# BackplaneBoard.net
KiCad netlist of a schematic drawn in EAGLE
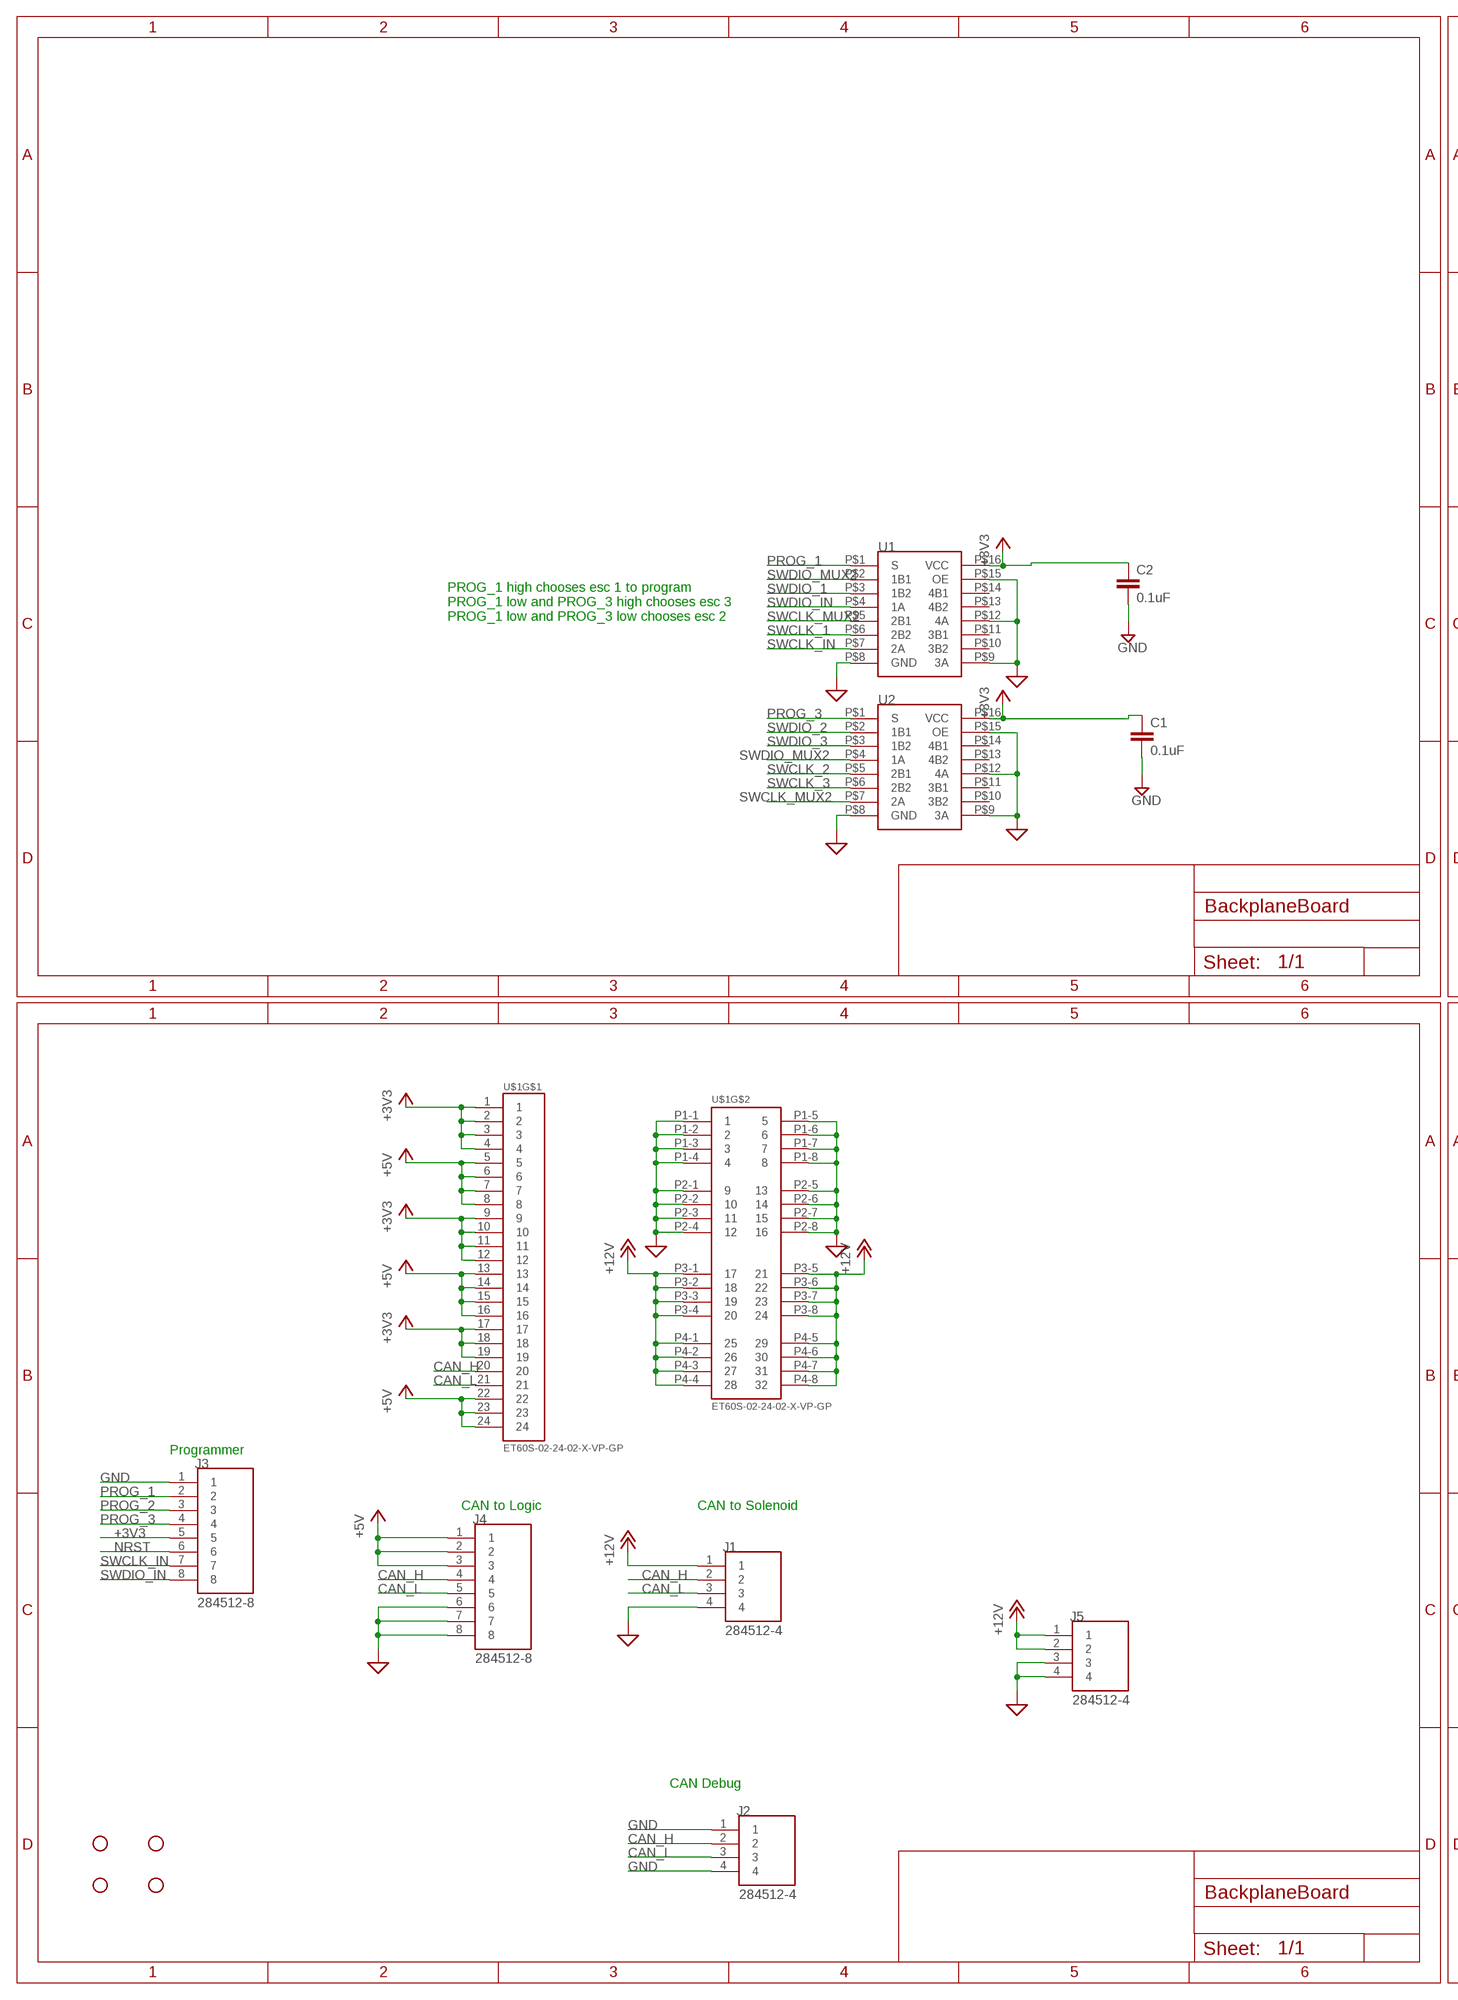
[diagram p0: schematic, sheet 1, part 1 of 2]
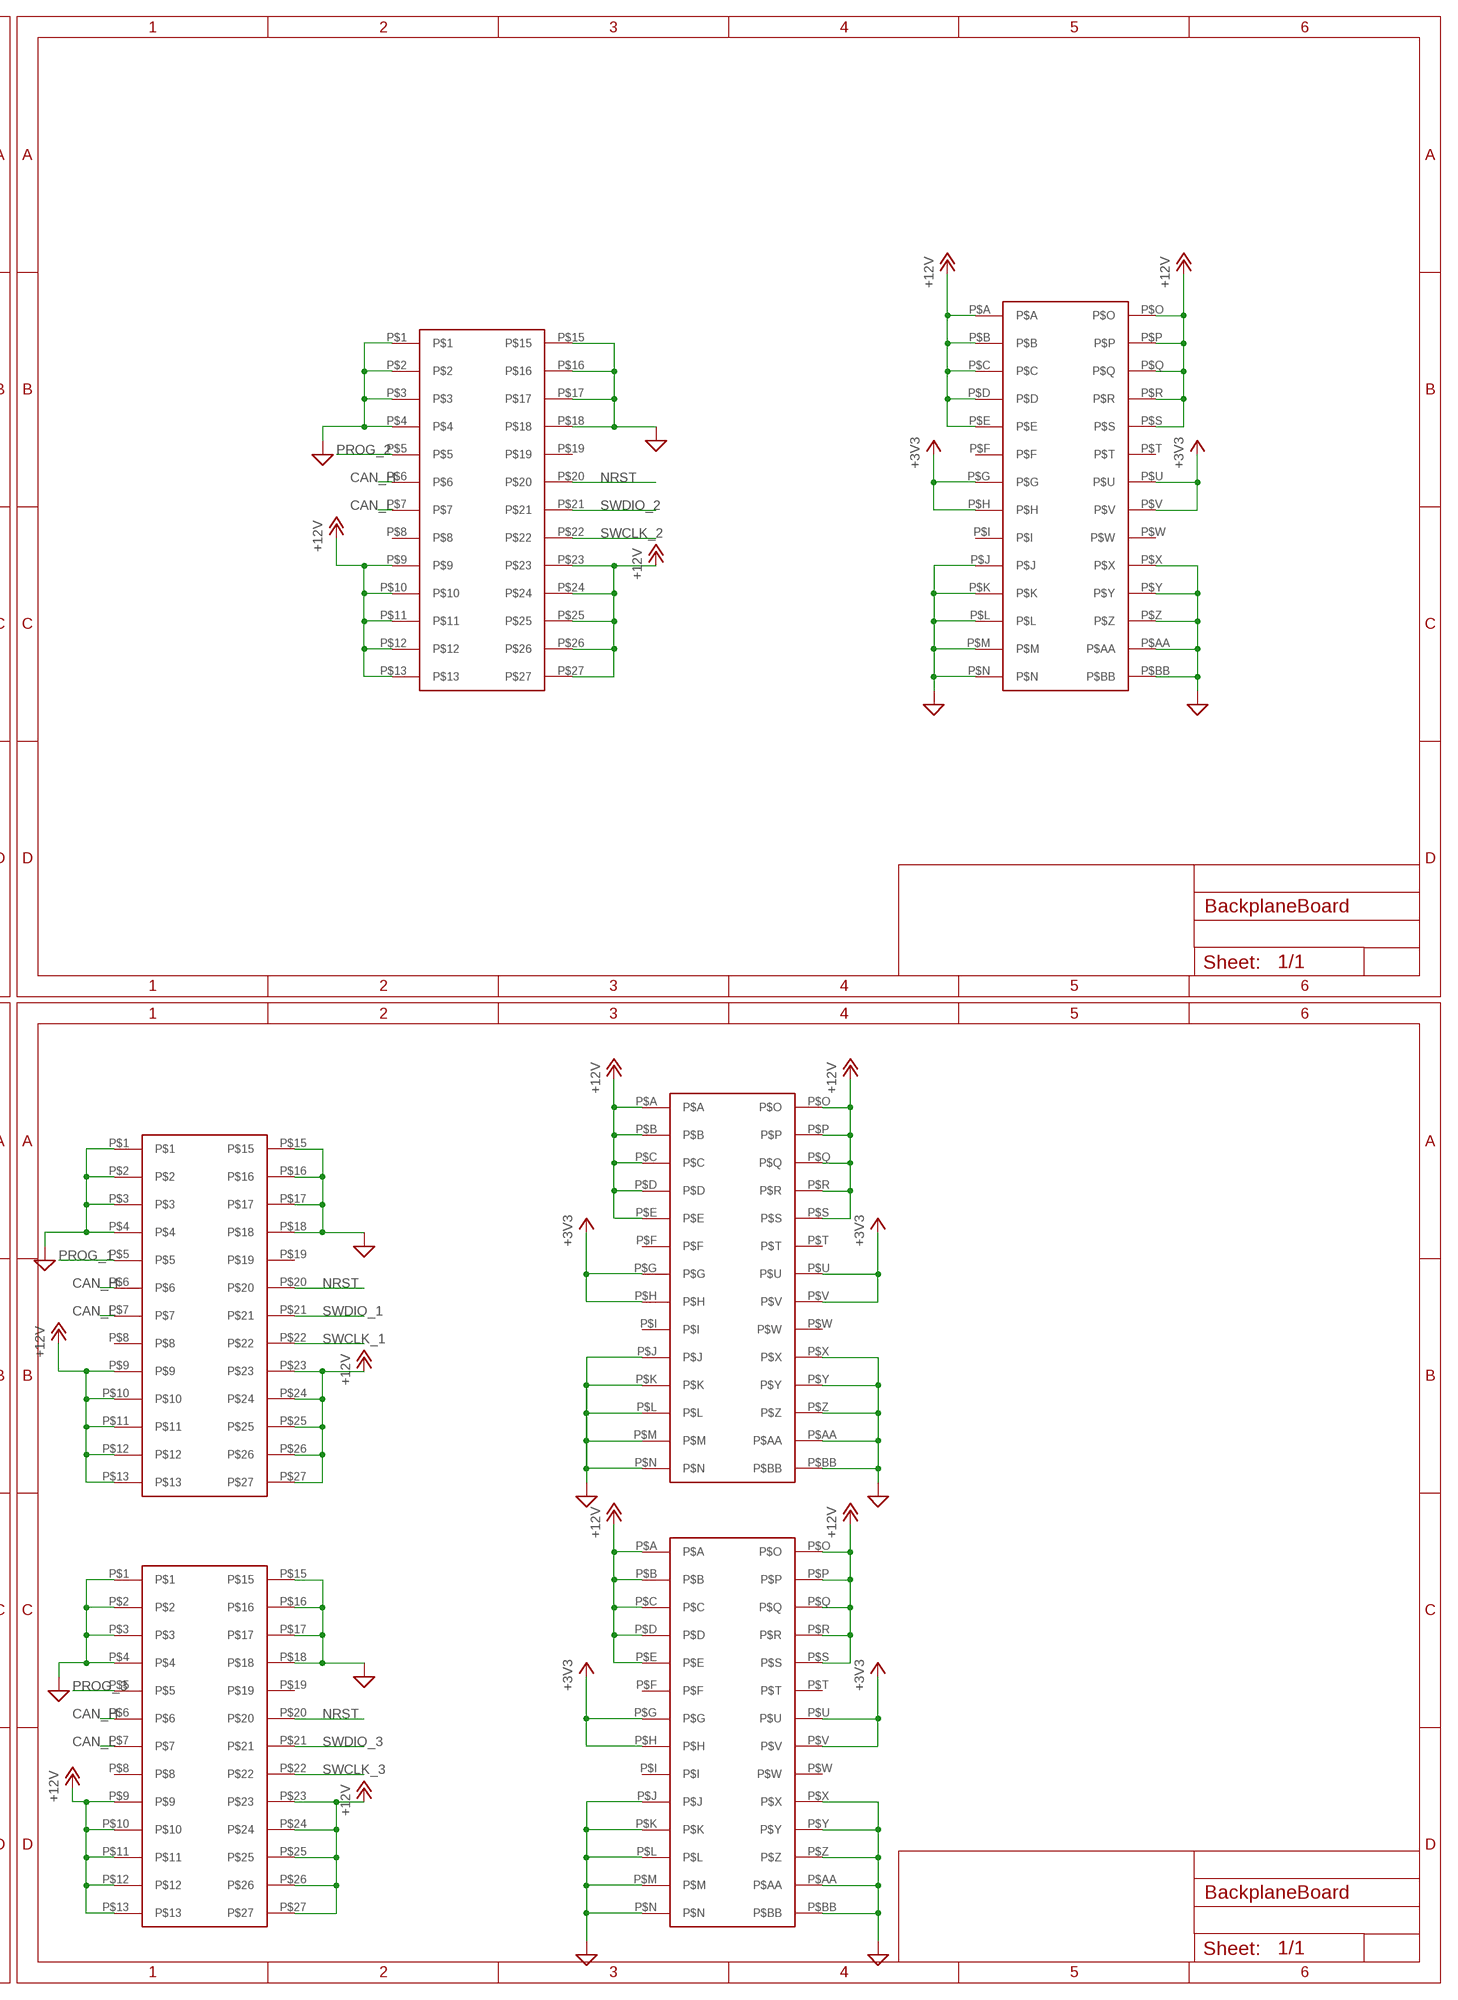
[diagram p1: schematic, sheet 1, part 2 of 2]

(export (version "E")
  (design (tool "Eeschema 10.0.6"))
  (components
    (comp (ref "C1")
      (value "0.1uF")
      (footprint "eagle-import:0603")
      (libsource (lib "eagle-import") (part "0.1UF-0603-25V-(+80/-20%)"))
    )
    (comp (ref "C2")
      (value "0.1uF")
      (footprint "eagle-import:0603")
      (libsource (lib "eagle-import") (part "0.1UF-0603-25V-(+80/-20%)"))
    )
    (comp (ref "H1")
      (value "STAND-OFF")
      (footprint "eagle-import:STAND-OFF")
      (libsource (lib "eagle-import") (part "STAND-OFF"))
    )
    (comp (ref "H2")
      (value "STAND-OFF")
      (footprint "eagle-import:STAND-OFF")
      (libsource (lib "eagle-import") (part "STAND-OFF"))
    )
    (comp (ref "H3")
      (value "STAND-OFF")
      (footprint "eagle-import:STAND-OFF")
      (libsource (lib "eagle-import") (part "STAND-OFF"))
    )
    (comp (ref "H4")
      (value "STAND-OFF")
      (footprint "eagle-import:STAND-OFF")
      (libsource (lib "eagle-import") (part "STAND-OFF"))
    )
    (comp (ref "J1")
      (value "284512-4")
      (footprint "eagle-import:TE_284512-4")
      (fields (field (name "MANUFACTURER") "TE"))
      (libsource (lib "eagle-import") (part "284512-4"))
    )
    (comp (ref "J2")
      (value "284512-4")
      (footprint "eagle-import:TE_284512-4")
      (fields (field (name "MANUFACTURER") "TE"))
      (libsource (lib "eagle-import") (part "284512-4"))
    )
    (comp (ref "J3")
      (value "284512-8")
      (footprint "eagle-import:TE_284512-8")
      (fields (field (name "MANUFACTURER") "TE"))
      (libsource (lib "eagle-import") (part "284512-8"))
    )
    (comp (ref "J4")
      (value "284512-8")
      (footprint "eagle-import:TE_284512-8")
      (fields (field (name "MANUFACTURER") "TE"))
      (libsource (lib "eagle-import") (part "284512-8"))
    )
    (comp (ref "J5")
      (value "284512-4")
      (footprint "eagle-import:TE_284512-4")
      (fields (field (name "MANUFACTURER") "TE"))
      (libsource (lib "eagle-import") (part "284512-4"))
    )
    (comp (ref "U$1")
      (value "ET60S-02-24-02-X-VP-GP")
      (footprint "eagle-import:ET60S-02-24-02-X-VP-GP")
      (libsource (lib "eagle-import") (part "ET60S-02-24-02-X-VP-GP"))
    )
    (comp (ref "U$2")
      (value "ESC2BACKPLANE")
      (footprint "eagle-import:ESC2BACKPLANE_WHOLE")
      (libsource (lib "eagle-import") (part "ESC2BACKPLANE"))
    )
    (comp (ref "U$3")
      (value "ESC2BACKPLANE")
      (footprint "eagle-import:ESC2BACKPLANE_WHOLE")
      (libsource (lib "eagle-import") (part "ESC2BACKPLANE"))
    )
    (comp (ref "U$4")
      (value "ESC2BACKPLANE")
      (footprint "eagle-import:ESC2BACKPLANE_WHOLE")
      (libsource (lib "eagle-import") (part "ESC2BACKPLANE"))
    )
    (comp (ref "U1")
      (value "SN74CBTLV3257PWR")
      (footprint "eagle-import:SN74CBTLV3257PWR")
      (libsource (lib "eagle-import") (part "SN74CBTLV3257PWR"))
    )
    (comp (ref "U2")
      (value "SN74CBTLV3257PWR")
      (footprint "eagle-import:SN74CBTLV3257PWR")
      (libsource (lib "eagle-import") (part "SN74CBTLV3257PWR"))
    )
  )
  (nets
    (net (code "1") (name "+3V3") (class "Default")
      (node (ref "C1") (pin "1") (pinfunction "1_1") (pintype "passive"))
      (node (ref "C2") (pin "1") (pinfunction "1_1") (pintype "passive"))
      (node (ref "J3") (pin "5") (pinfunction "5_5") (pintype "passive"))
      (node (ref "U$1") (pin "1") (pinfunction "1_1") (pintype "bidirectional"))
      (node (ref "U$1") (pin "10") (pinfunction "10_10") (pintype "bidirectional"))
      (node (ref "U$1") (pin "11") (pinfunction "11_11") (pintype "bidirectional"))
      (node (ref "U$1") (pin "12") (pinfunction "12_12") (pintype "bidirectional"))
      (node (ref "U$1") (pin "17") (pinfunction "17_17") (pintype "bidirectional"))
      (node (ref "U$1") (pin "18") (pinfunction "18_18") (pintype "bidirectional"))
      (node (ref "U$1") (pin "19") (pinfunction "19_19") (pintype "bidirectional"))
      (node (ref "U$1") (pin "2") (pinfunction "2_2") (pintype "bidirectional"))
      (node (ref "U$1") (pin "3") (pinfunction "3_3") (pintype "bidirectional"))
      (node (ref "U$1") (pin "4") (pinfunction "4_4") (pintype "bidirectional"))
      (node (ref "U$1") (pin "9") (pinfunction "9_9") (pintype "bidirectional"))
      (node (ref "U$2") (pin "P$G") (pinfunction "P$G_P$G") (pintype "bidirectional"))
      (node (ref "U$2") (pin "P$H") (pinfunction "P$H_P$H") (pintype "bidirectional"))
      (node (ref "U$2") (pin "P$U") (pinfunction "P$U_P$U") (pintype "bidirectional"))
      (node (ref "U$2") (pin "P$V") (pinfunction "P$V_P$V") (pintype "bidirectional"))
      (node (ref "U$3") (pin "P$G") (pinfunction "P$G_P$G") (pintype "bidirectional"))
      (node (ref "U$3") (pin "P$H") (pinfunction "P$H_P$H") (pintype "bidirectional"))
      (node (ref "U$3") (pin "P$U") (pinfunction "P$U_P$U") (pintype "bidirectional"))
      (node (ref "U$3") (pin "P$V") (pinfunction "P$V_P$V") (pintype "bidirectional"))
      (node (ref "U$4") (pin "P$G") (pinfunction "P$G_P$G") (pintype "bidirectional"))
      (node (ref "U$4") (pin "P$H") (pinfunction "P$H_P$H") (pintype "bidirectional"))
      (node (ref "U$4") (pin "P$U") (pinfunction "P$U_P$U") (pintype "bidirectional"))
      (node (ref "U$4") (pin "P$V") (pinfunction "P$V_P$V") (pintype "bidirectional"))
      (node (ref "U1") (pin "P$16") (pinfunction "VCC_P$16") (pintype "bidirectional"))
      (node (ref "U2") (pin "P$16") (pinfunction "VCC_P$16") (pintype "bidirectional"))
    )
    (net (code "2") (name "+5V") (class "Default")
      (node (ref "J4") (pin "1") (pinfunction "1_1") (pintype "passive"))
      (node (ref "J4") (pin "2") (pinfunction "2_2") (pintype "passive"))
      (node (ref "J4") (pin "3") (pinfunction "3_3") (pintype "passive"))
      (node (ref "U$1") (pin "13") (pinfunction "13_13") (pintype "bidirectional"))
      (node (ref "U$1") (pin "14") (pinfunction "14_14") (pintype "bidirectional"))
      (node (ref "U$1") (pin "15") (pinfunction "15_15") (pintype "bidirectional"))
      (node (ref "U$1") (pin "16") (pinfunction "16_16") (pintype "bidirectional"))
      (node (ref "U$1") (pin "22") (pinfunction "22_22") (pintype "bidirectional"))
      (node (ref "U$1") (pin "23") (pinfunction "23_23") (pintype "bidirectional"))
      (node (ref "U$1") (pin "24") (pinfunction "24_24") (pintype "bidirectional"))
      (node (ref "U$1") (pin "5") (pinfunction "5_5") (pintype "bidirectional"))
      (node (ref "U$1") (pin "6") (pinfunction "6_6") (pintype "bidirectional"))
      (node (ref "U$1") (pin "7") (pinfunction "7_7") (pintype "bidirectional"))
      (node (ref "U$1") (pin "8") (pinfunction "8_8") (pintype "bidirectional"))
    )
    (net (code "3") (name "+12V") (class "Default")
      (node (ref "J1") (pin "1") (pinfunction "1_1") (pintype "passive"))
      (node (ref "J5") (pin "1") (pinfunction "1_1") (pintype "passive"))
      (node (ref "J5") (pin "2") (pinfunction "2_2") (pintype "passive"))
      (node (ref "U$1") (pin "P3-1") (pinfunction "17_P3-1") (pintype "bidirectional"))
      (node (ref "U$1") (pin "P3-2") (pinfunction "18_P3-2") (pintype "bidirectional"))
      (node (ref "U$1") (pin "P3-3") (pinfunction "19_P3-3") (pintype "bidirectional"))
      (node (ref "U$1") (pin "P3-4") (pinfunction "20_P3-4") (pintype "bidirectional"))
      (node (ref "U$1") (pin "P3-5") (pinfunction "21_P3-5") (pintype "bidirectional"))
      (node (ref "U$1") (pin "P3-6") (pinfunction "22_P3-6") (pintype "bidirectional"))
      (node (ref "U$1") (pin "P3-7") (pinfunction "23_P3-7") (pintype "bidirectional"))
      (node (ref "U$1") (pin "P3-8") (pinfunction "24_P3-8") (pintype "bidirectional"))
      (node (ref "U$1") (pin "P4-1") (pinfunction "25_P4-1") (pintype "bidirectional"))
      (node (ref "U$1") (pin "P4-2") (pinfunction "26_P4-2") (pintype "bidirectional"))
      (node (ref "U$1") (pin "P4-3") (pinfunction "27_P4-3") (pintype "bidirectional"))
      (node (ref "U$1") (pin "P4-4") (pinfunction "28_P4-4") (pintype "bidirectional"))
      (node (ref "U$1") (pin "P4-5") (pinfunction "29_P4-5") (pintype "bidirectional"))
      (node (ref "U$1") (pin "P4-6") (pinfunction "30_P4-6") (pintype "bidirectional"))
      (node (ref "U$1") (pin "P4-7") (pinfunction "31_P4-7") (pintype "bidirectional"))
      (node (ref "U$1") (pin "P4-8") (pinfunction "32_P4-8") (pintype "bidirectional"))
      (node (ref "U$2") (pin "P$10") (pinfunction "P$10_P$10") (pintype "bidirectional"))
      (node (ref "U$2") (pin "P$11") (pinfunction "P$11_P$11") (pintype "bidirectional"))
      (node (ref "U$2") (pin "P$12") (pinfunction "P$12_P$12") (pintype "bidirectional"))
      (node (ref "U$2") (pin "P$13") (pinfunction "P$13_P$13") (pintype "bidirectional"))
      (node (ref "U$2") (pin "P$23") (pinfunction "P$23_P$23") (pintype "bidirectional"))
      (node (ref "U$2") (pin "P$24") (pinfunction "P$24_P$24") (pintype "bidirectional"))
      (node (ref "U$2") (pin "P$25") (pinfunction "P$25_P$25") (pintype "bidirectional"))
      (node (ref "U$2") (pin "P$26") (pinfunction "P$26_P$26") (pintype "bidirectional"))
      (node (ref "U$2") (pin "P$27") (pinfunction "P$27_P$27") (pintype "bidirectional"))
      (node (ref "U$2") (pin "P$9") (pinfunction "P$9_P$9") (pintype "bidirectional"))
      (node (ref "U$2") (pin "P$A") (pinfunction "P$A_P$A") (pintype "bidirectional"))
      (node (ref "U$2") (pin "P$B") (pinfunction "P$B_P$B") (pintype "bidirectional"))
      (node (ref "U$2") (pin "P$C") (pinfunction "P$C_P$C") (pintype "bidirectional"))
      (node (ref "U$2") (pin "P$D") (pinfunction "P$D_P$D") (pintype "bidirectional"))
      (node (ref "U$2") (pin "P$E") (pinfunction "P$E_P$E") (pintype "bidirectional"))
      (node (ref "U$2") (pin "P$O") (pinfunction "P$O_P$O") (pintype "bidirectional"))
      (node (ref "U$2") (pin "P$P") (pinfunction "P$P_P$P") (pintype "bidirectional"))
      (node (ref "U$2") (pin "P$Q") (pinfunction "P$Q_P$Q") (pintype "bidirectional"))
      (node (ref "U$2") (pin "P$R") (pinfunction "P$R_P$R") (pintype "bidirectional"))
      (node (ref "U$2") (pin "P$S") (pinfunction "P$S_P$S") (pintype "bidirectional"))
      (node (ref "U$3") (pin "P$10") (pinfunction "P$10_P$10") (pintype "bidirectional"))
      (node (ref "U$3") (pin "P$11") (pinfunction "P$11_P$11") (pintype "bidirectional"))
      (node (ref "U$3") (pin "P$12") (pinfunction "P$12_P$12") (pintype "bidirectional"))
      (node (ref "U$3") (pin "P$13") (pinfunction "P$13_P$13") (pintype "bidirectional"))
      (node (ref "U$3") (pin "P$23") (pinfunction "P$23_P$23") (pintype "bidirectional"))
      (node (ref "U$3") (pin "P$24") (pinfunction "P$24_P$24") (pintype "bidirectional"))
      (node (ref "U$3") (pin "P$25") (pinfunction "P$25_P$25") (pintype "bidirectional"))
      (node (ref "U$3") (pin "P$26") (pinfunction "P$26_P$26") (pintype "bidirectional"))
      (node (ref "U$3") (pin "P$27") (pinfunction "P$27_P$27") (pintype "bidirectional"))
      (node (ref "U$3") (pin "P$9") (pinfunction "P$9_P$9") (pintype "bidirectional"))
      (node (ref "U$3") (pin "P$A") (pinfunction "P$A_P$A") (pintype "bidirectional"))
      (node (ref "U$3") (pin "P$B") (pinfunction "P$B_P$B") (pintype "bidirectional"))
      (node (ref "U$3") (pin "P$C") (pinfunction "P$C_P$C") (pintype "bidirectional"))
      (node (ref "U$3") (pin "P$D") (pinfunction "P$D_P$D") (pintype "bidirectional"))
      (node (ref "U$3") (pin "P$E") (pinfunction "P$E_P$E") (pintype "bidirectional"))
      (node (ref "U$3") (pin "P$O") (pinfunction "P$O_P$O") (pintype "bidirectional"))
      (node (ref "U$3") (pin "P$P") (pinfunction "P$P_P$P") (pintype "bidirectional"))
      (node (ref "U$3") (pin "P$Q") (pinfunction "P$Q_P$Q") (pintype "bidirectional"))
      (node (ref "U$3") (pin "P$R") (pinfunction "P$R_P$R") (pintype "bidirectional"))
      (node (ref "U$3") (pin "P$S") (pinfunction "P$S_P$S") (pintype "bidirectional"))
      (node (ref "U$4") (pin "P$10") (pinfunction "P$10_P$10") (pintype "bidirectional"))
      (node (ref "U$4") (pin "P$11") (pinfunction "P$11_P$11") (pintype "bidirectional"))
      (node (ref "U$4") (pin "P$12") (pinfunction "P$12_P$12") (pintype "bidirectional"))
      (node (ref "U$4") (pin "P$13") (pinfunction "P$13_P$13") (pintype "bidirectional"))
      (node (ref "U$4") (pin "P$23") (pinfunction "P$23_P$23") (pintype "bidirectional"))
      (node (ref "U$4") (pin "P$24") (pinfunction "P$24_P$24") (pintype "bidirectional"))
      (node (ref "U$4") (pin "P$25") (pinfunction "P$25_P$25") (pintype "bidirectional"))
      (node (ref "U$4") (pin "P$26") (pinfunction "P$26_P$26") (pintype "bidirectional"))
      (node (ref "U$4") (pin "P$27") (pinfunction "P$27_P$27") (pintype "bidirectional"))
      (node (ref "U$4") (pin "P$9") (pinfunction "P$9_P$9") (pintype "bidirectional"))
      (node (ref "U$4") (pin "P$A") (pinfunction "P$A_P$A") (pintype "bidirectional"))
      (node (ref "U$4") (pin "P$B") (pinfunction "P$B_P$B") (pintype "bidirectional"))
      (node (ref "U$4") (pin "P$C") (pinfunction "P$C_P$C") (pintype "bidirectional"))
      (node (ref "U$4") (pin "P$D") (pinfunction "P$D_P$D") (pintype "bidirectional"))
      (node (ref "U$4") (pin "P$E") (pinfunction "P$E_P$E") (pintype "bidirectional"))
      (node (ref "U$4") (pin "P$O") (pinfunction "P$O_P$O") (pintype "bidirectional"))
      (node (ref "U$4") (pin "P$P") (pinfunction "P$P_P$P") (pintype "bidirectional"))
      (node (ref "U$4") (pin "P$Q") (pinfunction "P$Q_P$Q") (pintype "bidirectional"))
      (node (ref "U$4") (pin "P$R") (pinfunction "P$R_P$R") (pintype "bidirectional"))
      (node (ref "U$4") (pin "P$S") (pinfunction "P$S_P$S") (pintype "bidirectional"))
    )
    (net (code "4") (name "/CAN_H") (class "Default")
      (node (ref "J1") (pin "2") (pinfunction "2_2") (pintype "passive"))
      (node (ref "J2") (pin "2") (pinfunction "2_2") (pintype "passive"))
      (node (ref "J4") (pin "4") (pinfunction "4_4") (pintype "passive"))
      (node (ref "U$1") (pin "20") (pinfunction "20_20") (pintype "bidirectional"))
      (node (ref "U$2") (pin "P$6") (pinfunction "P$6_P$6") (pintype "bidirectional"))
      (node (ref "U$3") (pin "P$6") (pinfunction "P$6_P$6") (pintype "bidirectional"))
      (node (ref "U$4") (pin "P$6") (pinfunction "P$6_P$6") (pintype "bidirectional"))
    )
    (net (code "5") (name "/CAN_L") (class "Default")
      (node (ref "J1") (pin "3") (pinfunction "3_3") (pintype "passive"))
      (node (ref "J2") (pin "3") (pinfunction "3_3") (pintype "passive"))
      (node (ref "J4") (pin "5") (pinfunction "5_5") (pintype "passive"))
      (node (ref "U$1") (pin "21") (pinfunction "21_21") (pintype "bidirectional"))
      (node (ref "U$2") (pin "P$7") (pinfunction "P$7_P$7") (pintype "bidirectional"))
      (node (ref "U$3") (pin "P$7") (pinfunction "P$7_P$7") (pintype "bidirectional"))
      (node (ref "U$4") (pin "P$7") (pinfunction "P$7_P$7") (pintype "bidirectional"))
    )
    (net (code "6") (name "/NRST") (class "Default")
      (node (ref "J3") (pin "6") (pinfunction "6_6") (pintype "passive"))
      (node (ref "U$2") (pin "P$20") (pinfunction "P$20_P$20") (pintype "bidirectional"))
      (node (ref "U$3") (pin "P$20") (pinfunction "P$20_P$20") (pintype "bidirectional"))
      (node (ref "U$4") (pin "P$20") (pinfunction "P$20_P$20") (pintype "bidirectional"))
    )
    (net (code "7") (name "/PROG_1") (class "Default")
      (node (ref "J3") (pin "2") (pinfunction "2_2") (pintype "passive"))
      (node (ref "U$2") (pin "P$5") (pinfunction "P$5_P$5") (pintype "bidirectional"))
      (node (ref "U1") (pin "P$1") (pinfunction "S_P$1") (pintype "bidirectional"))
    )
    (net (code "8") (name "/PROG_2") (class "Default")
      (node (ref "J3") (pin "3") (pinfunction "3_3") (pintype "passive"))
      (node (ref "U$3") (pin "P$5") (pinfunction "P$5_P$5") (pintype "bidirectional"))
    )
    (net (code "9") (name "/PROG_3") (class "Default")
      (node (ref "J3") (pin "4") (pinfunction "4_4") (pintype "passive"))
      (node (ref "U$4") (pin "P$5") (pinfunction "P$5_P$5") (pintype "bidirectional"))
      (node (ref "U2") (pin "P$1") (pinfunction "S_P$1") (pintype "bidirectional"))
    )
    (net (code "10") (name "/SWCLK_1") (class "Default")
      (node (ref "U$2") (pin "P$22") (pinfunction "P$22_P$22") (pintype "bidirectional"))
      (node (ref "U1") (pin "P$6") (pinfunction "2B2_P$6") (pintype "bidirectional"))
    )
    (net (code "11") (name "/SWCLK_2") (class "Default")
      (node (ref "U$3") (pin "P$22") (pinfunction "P$22_P$22") (pintype "bidirectional"))
      (node (ref "U2") (pin "P$5") (pinfunction "2B1_P$5") (pintype "bidirectional"))
    )
    (net (code "12") (name "/SWCLK_3") (class "Default")
      (node (ref "U$4") (pin "P$22") (pinfunction "P$22_P$22") (pintype "bidirectional"))
      (node (ref "U2") (pin "P$6") (pinfunction "2B2_P$6") (pintype "bidirectional"))
    )
    (net (code "13") (name "/SWCLK_IN") (class "Default")
      (node (ref "J3") (pin "7") (pinfunction "7_7") (pintype "passive"))
      (node (ref "U1") (pin "P$7") (pinfunction "2A_P$7") (pintype "bidirectional"))
    )
    (net (code "14") (name "/SWCLK_MUX2") (class "Default")
      (node (ref "U1") (pin "P$5") (pinfunction "2B1_P$5") (pintype "bidirectional"))
      (node (ref "U2") (pin "P$7") (pinfunction "2A_P$7") (pintype "bidirectional"))
    )
    (net (code "15") (name "/SWDIO_1") (class "Default")
      (node (ref "U$2") (pin "P$21") (pinfunction "P$21_P$21") (pintype "bidirectional"))
      (node (ref "U1") (pin "P$3") (pinfunction "1B2_P$3") (pintype "bidirectional"))
    )
    (net (code "16") (name "/SWDIO_2") (class "Default")
      (node (ref "U$3") (pin "P$21") (pinfunction "P$21_P$21") (pintype "bidirectional"))
      (node (ref "U2") (pin "P$2") (pinfunction "1B1_P$2") (pintype "bidirectional"))
    )
    (net (code "17") (name "/SWDIO_3") (class "Default")
      (node (ref "U$4") (pin "P$21") (pinfunction "P$21_P$21") (pintype "bidirectional"))
      (node (ref "U2") (pin "P$3") (pinfunction "1B2_P$3") (pintype "bidirectional"))
    )
    (net (code "18") (name "/SWDIO_IN") (class "Default")
      (node (ref "J3") (pin "8") (pinfunction "8_8") (pintype "passive"))
      (node (ref "U1") (pin "P$4") (pinfunction "1A_P$4") (pintype "bidirectional"))
    )
    (net (code "19") (name "/SWDIO_MUX2") (class "Default")
      (node (ref "U1") (pin "P$2") (pinfunction "1B1_P$2") (pintype "bidirectional"))
      (node (ref "U2") (pin "P$4") (pinfunction "1A_P$4") (pintype "bidirectional"))
    )
    (net (code "20") (name "GND") (class "Default")
      (node (ref "C1") (pin "2") (pinfunction "2_2") (pintype "passive"))
      (node (ref "C2") (pin "2") (pinfunction "2_2") (pintype "passive"))
      (node (ref "J1") (pin "4") (pinfunction "4_4") (pintype "passive"))
      (node (ref "J2") (pin "1") (pinfunction "1_1") (pintype "passive"))
      (node (ref "J2") (pin "4") (pinfunction "4_4") (pintype "passive"))
      (node (ref "J3") (pin "1") (pinfunction "1_1") (pintype "passive"))
      (node (ref "J4") (pin "6") (pinfunction "6_6") (pintype "passive"))
      (node (ref "J4") (pin "7") (pinfunction "7_7") (pintype "passive"))
      (node (ref "J4") (pin "8") (pinfunction "8_8") (pintype "passive"))
      (node (ref "J5") (pin "3") (pinfunction "3_3") (pintype "passive"))
      (node (ref "J5") (pin "4") (pinfunction "4_4") (pintype "passive"))
      (node (ref "U$1") (pin "P1-1") (pinfunction "1_P1-1") (pintype "bidirectional"))
      (node (ref "U$1") (pin "P1-2") (pinfunction "2_P1-2") (pintype "bidirectional"))
      (node (ref "U$1") (pin "P1-3") (pinfunction "3_P1-3") (pintype "bidirectional"))
      (node (ref "U$1") (pin "P1-4") (pinfunction "4_P1-4") (pintype "bidirectional"))
      (node (ref "U$1") (pin "P1-5") (pinfunction "5_P1-5") (pintype "bidirectional"))
      (node (ref "U$1") (pin "P1-6") (pinfunction "6_P1-6") (pintype "bidirectional"))
      (node (ref "U$1") (pin "P1-7") (pinfunction "7_P1-7") (pintype "bidirectional"))
      (node (ref "U$1") (pin "P1-8") (pinfunction "8_P1-8") (pintype "bidirectional"))
      (node (ref "U$1") (pin "P2-1") (pinfunction "9_P2-1") (pintype "bidirectional"))
      (node (ref "U$1") (pin "P2-2") (pinfunction "10_P2-2") (pintype "bidirectional"))
      (node (ref "U$1") (pin "P2-3") (pinfunction "11_P2-3") (pintype "bidirectional"))
      (node (ref "U$1") (pin "P2-4") (pinfunction "12_P2-4") (pintype "bidirectional"))
      (node (ref "U$1") (pin "P2-5") (pinfunction "13_P2-5") (pintype "bidirectional"))
      (node (ref "U$1") (pin "P2-6") (pinfunction "14_P2-6") (pintype "bidirectional"))
      (node (ref "U$1") (pin "P2-7") (pinfunction "15_P2-7") (pintype "bidirectional"))
      (node (ref "U$1") (pin "P2-8") (pinfunction "16_P2-8") (pintype "bidirectional"))
      (node (ref "U$2") (pin "P$1") (pinfunction "P$1_P$1") (pintype "bidirectional"))
      (node (ref "U$2") (pin "P$15") (pinfunction "P$15_P$15") (pintype "bidirectional"))
      (node (ref "U$2") (pin "P$16") (pinfunction "P$16_P$16") (pintype "bidirectional"))
      (node (ref "U$2") (pin "P$17") (pinfunction "P$17_P$17") (pintype "bidirectional"))
      (node (ref "U$2") (pin "P$18") (pinfunction "P$18_P$18") (pintype "bidirectional"))
      (node (ref "U$2") (pin "P$2") (pinfunction "P$2_P$2") (pintype "bidirectional"))
      (node (ref "U$2") (pin "P$3") (pinfunction "P$3_P$3") (pintype "bidirectional"))
      (node (ref "U$2") (pin "P$4") (pinfunction "P$4_P$4") (pintype "bidirectional"))
      (node (ref "U$2") (pin "P$AA") (pinfunction "P$AA_P$AA") (pintype "bidirectional"))
      (node (ref "U$2") (pin "P$BB") (pinfunction "P$BB_P$BB") (pintype "bidirectional"))
      (node (ref "U$2") (pin "P$J") (pinfunction "P$J_P$J") (pintype "bidirectional"))
      (node (ref "U$2") (pin "P$K") (pinfunction "P$K_P$K") (pintype "bidirectional"))
      (node (ref "U$2") (pin "P$L") (pinfunction "P$L_P$L") (pintype "bidirectional"))
      (node (ref "U$2") (pin "P$M") (pinfunction "P$M_P$M") (pintype "bidirectional"))
      (node (ref "U$2") (pin "P$N") (pinfunction "P$N_P$N") (pintype "bidirectional"))
      (node (ref "U$2") (pin "P$X") (pinfunction "P$X_P$X") (pintype "bidirectional"))
      (node (ref "U$2") (pin "P$Y") (pinfunction "P$Y_P$Y") (pintype "bidirectional"))
      (node (ref "U$2") (pin "P$Z") (pinfunction "P$Z_P$Z") (pintype "bidirectional"))
      (node (ref "U$3") (pin "P$1") (pinfunction "P$1_P$1") (pintype "bidirectional"))
      (node (ref "U$3") (pin "P$15") (pinfunction "P$15_P$15") (pintype "bidirectional"))
      (node (ref "U$3") (pin "P$16") (pinfunction "P$16_P$16") (pintype "bidirectional"))
      (node (ref "U$3") (pin "P$17") (pinfunction "P$17_P$17") (pintype "bidirectional"))
      (node (ref "U$3") (pin "P$18") (pinfunction "P$18_P$18") (pintype "bidirectional"))
      (node (ref "U$3") (pin "P$2") (pinfunction "P$2_P$2") (pintype "bidirectional"))
      (node (ref "U$3") (pin "P$3") (pinfunction "P$3_P$3") (pintype "bidirectional"))
      (node (ref "U$3") (pin "P$4") (pinfunction "P$4_P$4") (pintype "bidirectional"))
      (node (ref "U$3") (pin "P$AA") (pinfunction "P$AA_P$AA") (pintype "bidirectional"))
      (node (ref "U$3") (pin "P$BB") (pinfunction "P$BB_P$BB") (pintype "bidirectional"))
      (node (ref "U$3") (pin "P$J") (pinfunction "P$J_P$J") (pintype "bidirectional"))
      (node (ref "U$3") (pin "P$K") (pinfunction "P$K_P$K") (pintype "bidirectional"))
      (node (ref "U$3") (pin "P$L") (pinfunction "P$L_P$L") (pintype "bidirectional"))
      (node (ref "U$3") (pin "P$M") (pinfunction "P$M_P$M") (pintype "bidirectional"))
      (node (ref "U$3") (pin "P$N") (pinfunction "P$N_P$N") (pintype "bidirectional"))
      (node (ref "U$3") (pin "P$X") (pinfunction "P$X_P$X") (pintype "bidirectional"))
      (node (ref "U$3") (pin "P$Y") (pinfunction "P$Y_P$Y") (pintype "bidirectional"))
      (node (ref "U$3") (pin "P$Z") (pinfunction "P$Z_P$Z") (pintype "bidirectional"))
      (node (ref "U$4") (pin "P$1") (pinfunction "P$1_P$1") (pintype "bidirectional"))
      (node (ref "U$4") (pin "P$15") (pinfunction "P$15_P$15") (pintype "bidirectional"))
      (node (ref "U$4") (pin "P$16") (pinfunction "P$16_P$16") (pintype "bidirectional"))
      (node (ref "U$4") (pin "P$17") (pinfunction "P$17_P$17") (pintype "bidirectional"))
      (node (ref "U$4") (pin "P$18") (pinfunction "P$18_P$18") (pintype "bidirectional"))
      (node (ref "U$4") (pin "P$2") (pinfunction "P$2_P$2") (pintype "bidirectional"))
      (node (ref "U$4") (pin "P$3") (pinfunction "P$3_P$3") (pintype "bidirectional"))
      (node (ref "U$4") (pin "P$4") (pinfunction "P$4_P$4") (pintype "bidirectional"))
      (node (ref "U$4") (pin "P$AA") (pinfunction "P$AA_P$AA") (pintype "bidirectional"))
      (node (ref "U$4") (pin "P$BB") (pinfunction "P$BB_P$BB") (pintype "bidirectional"))
      (node (ref "U$4") (pin "P$J") (pinfunction "P$J_P$J") (pintype "bidirectional"))
      (node (ref "U$4") (pin "P$K") (pinfunction "P$K_P$K") (pintype "bidirectional"))
      (node (ref "U$4") (pin "P$L") (pinfunction "P$L_P$L") (pintype "bidirectional"))
      (node (ref "U$4") (pin "P$M") (pinfunction "P$M_P$M") (pintype "bidirectional"))
      (node (ref "U$4") (pin "P$N") (pinfunction "P$N_P$N") (pintype "bidirectional"))
      (node (ref "U$4") (pin "P$X") (pinfunction "P$X_P$X") (pintype "bidirectional"))
      (node (ref "U$4") (pin "P$Y") (pinfunction "P$Y_P$Y") (pintype "bidirectional"))
      (node (ref "U$4") (pin "P$Z") (pinfunction "P$Z_P$Z") (pintype "bidirectional"))
      (node (ref "U1") (pin "P$12") (pinfunction "4A_P$12") (pintype "bidirectional"))
      (node (ref "U1") (pin "P$15") (pinfunction "OE_P$15") (pintype "bidirectional"))
      (node (ref "U1") (pin "P$8") (pinfunction "GND_P$8") (pintype "bidirectional"))
      (node (ref "U1") (pin "P$9") (pinfunction "3A_P$9") (pintype "bidirectional"))
      (node (ref "U2") (pin "P$12") (pinfunction "4A_P$12") (pintype "bidirectional"))
      (node (ref "U2") (pin "P$15") (pinfunction "OE_P$15") (pintype "bidirectional"))
      (node (ref "U2") (pin "P$8") (pinfunction "GND_P$8") (pintype "bidirectional"))
      (node (ref "U2") (pin "P$9") (pinfunction "3A_P$9") (pintype "bidirectional"))
    )
    (net (code "21") (name "unconnected-(U$2-PadP$8)") (class "Default")
      (node (ref "U$2") (pin "P$8") (pinfunction "P$8_P$8") (pintype "bidirectional"))
    )
    (net (code "22") (name "unconnected-(U$2-PadP$19)") (class "Default")
      (node (ref "U$2") (pin "P$19") (pinfunction "P$19_P$19") (pintype "bidirectional"))
    )
    (net (code "23") (name "unconnected-(U$2-PadP$F)") (class "Default")
      (node (ref "U$2") (pin "P$F") (pinfunction "P$F_P$F") (pintype "bidirectional"))
    )
    (net (code "24") (name "unconnected-(U$2-PadP$I)") (class "Default")
      (node (ref "U$2") (pin "P$I") (pinfunction "P$I_P$I") (pintype "bidirectional"))
    )
    (net (code "25") (name "unconnected-(U$2-PadP$T)") (class "Default")
      (node (ref "U$2") (pin "P$T") (pinfunction "P$T_P$T") (pintype "bidirectional"))
    )
    (net (code "26") (name "unconnected-(U$2-PadP$W)") (class "Default")
      (node (ref "U$2") (pin "P$W") (pinfunction "P$W_P$W") (pintype "bidirectional"))
    )
    (net (code "27") (name "unconnected-(U$3-PadP$8)") (class "Default")
      (node (ref "U$3") (pin "P$8") (pinfunction "P$8_P$8") (pintype "bidirectional"))
    )
    (net (code "28") (name "unconnected-(U$3-PadP$19)") (class "Default")
      (node (ref "U$3") (pin "P$19") (pinfunction "P$19_P$19") (pintype "bidirectional"))
    )
    (net (code "29") (name "unconnected-(U$3-PadP$F)") (class "Default")
      (node (ref "U$3") (pin "P$F") (pinfunction "P$F_P$F") (pintype "bidirectional"))
    )
    (net (code "30") (name "unconnected-(U$3-PadP$I)") (class "Default")
      (node (ref "U$3") (pin "P$I") (pinfunction "P$I_P$I") (pintype "bidirectional"))
    )
    (net (code "31") (name "unconnected-(U$3-PadP$T)") (class "Default")
      (node (ref "U$3") (pin "P$T") (pinfunction "P$T_P$T") (pintype "bidirectional"))
    )
    (net (code "32") (name "unconnected-(U$3-PadP$W)") (class "Default")
      (node (ref "U$3") (pin "P$W") (pinfunction "P$W_P$W") (pintype "bidirectional"))
    )
    (net (code "33") (name "unconnected-(U$4-PadP$8)") (class "Default")
      (node (ref "U$4") (pin "P$8") (pinfunction "P$8_P$8") (pintype "bidirectional"))
    )
    (net (code "34") (name "unconnected-(U$4-PadP$19)") (class "Default")
      (node (ref "U$4") (pin "P$19") (pinfunction "P$19_P$19") (pintype "bidirectional"))
    )
    (net (code "35") (name "unconnected-(U$4-PadP$F)") (class "Default")
      (node (ref "U$4") (pin "P$F") (pinfunction "P$F_P$F") (pintype "bidirectional"))
    )
    (net (code "36") (name "unconnected-(U$4-PadP$I)") (class "Default")
      (node (ref "U$4") (pin "P$I") (pinfunction "P$I_P$I") (pintype "bidirectional"))
    )
    (net (code "37") (name "unconnected-(U$4-PadP$T)") (class "Default")
      (node (ref "U$4") (pin "P$T") (pinfunction "P$T_P$T") (pintype "bidirectional"))
    )
    (net (code "38") (name "unconnected-(U$4-PadP$W)") (class "Default")
      (node (ref "U$4") (pin "P$W") (pinfunction "P$W_P$W") (pintype "bidirectional"))
    )
    (net (code "39") (name "unconnected-(U1-3B1-PadP$11)") (class "Default")
      (node (ref "U1") (pin "P$11") (pinfunction "3B1_P$11") (pintype "bidirectional"))
    )
    (net (code "40") (name "unconnected-(U1-3B2-PadP$10)") (class "Default")
      (node (ref "U1") (pin "P$10") (pinfunction "3B2_P$10") (pintype "bidirectional"))
    )
    (net (code "41") (name "unconnected-(U1-4B1-PadP$14)") (class "Default")
      (node (ref "U1") (pin "P$14") (pinfunction "4B1_P$14") (pintype "bidirectional"))
    )
    (net (code "42") (name "unconnected-(U1-4B2-PadP$13)") (class "Default")
      (node (ref "U1") (pin "P$13") (pinfunction "4B2_P$13") (pintype "bidirectional"))
    )
    (net (code "43") (name "unconnected-(U2-3B1-PadP$11)") (class "Default")
      (node (ref "U2") (pin "P$11") (pinfunction "3B1_P$11") (pintype "bidirectional"))
    )
    (net (code "44") (name "unconnected-(U2-3B2-PadP$10)") (class "Default")
      (node (ref "U2") (pin "P$10") (pinfunction "3B2_P$10") (pintype "bidirectional"))
    )
    (net (code "45") (name "unconnected-(U2-4B1-PadP$14)") (class "Default")
      (node (ref "U2") (pin "P$14") (pinfunction "4B1_P$14") (pintype "bidirectional"))
    )
    (net (code "46") (name "unconnected-(U2-4B2-PadP$13)") (class "Default")
      (node (ref "U2") (pin "P$13") (pinfunction "4B2_P$13") (pintype "bidirectional"))
    )
  )
)
